# interaction_agronautes.net
KiCad netlist of a schematic drawn in EAGLE
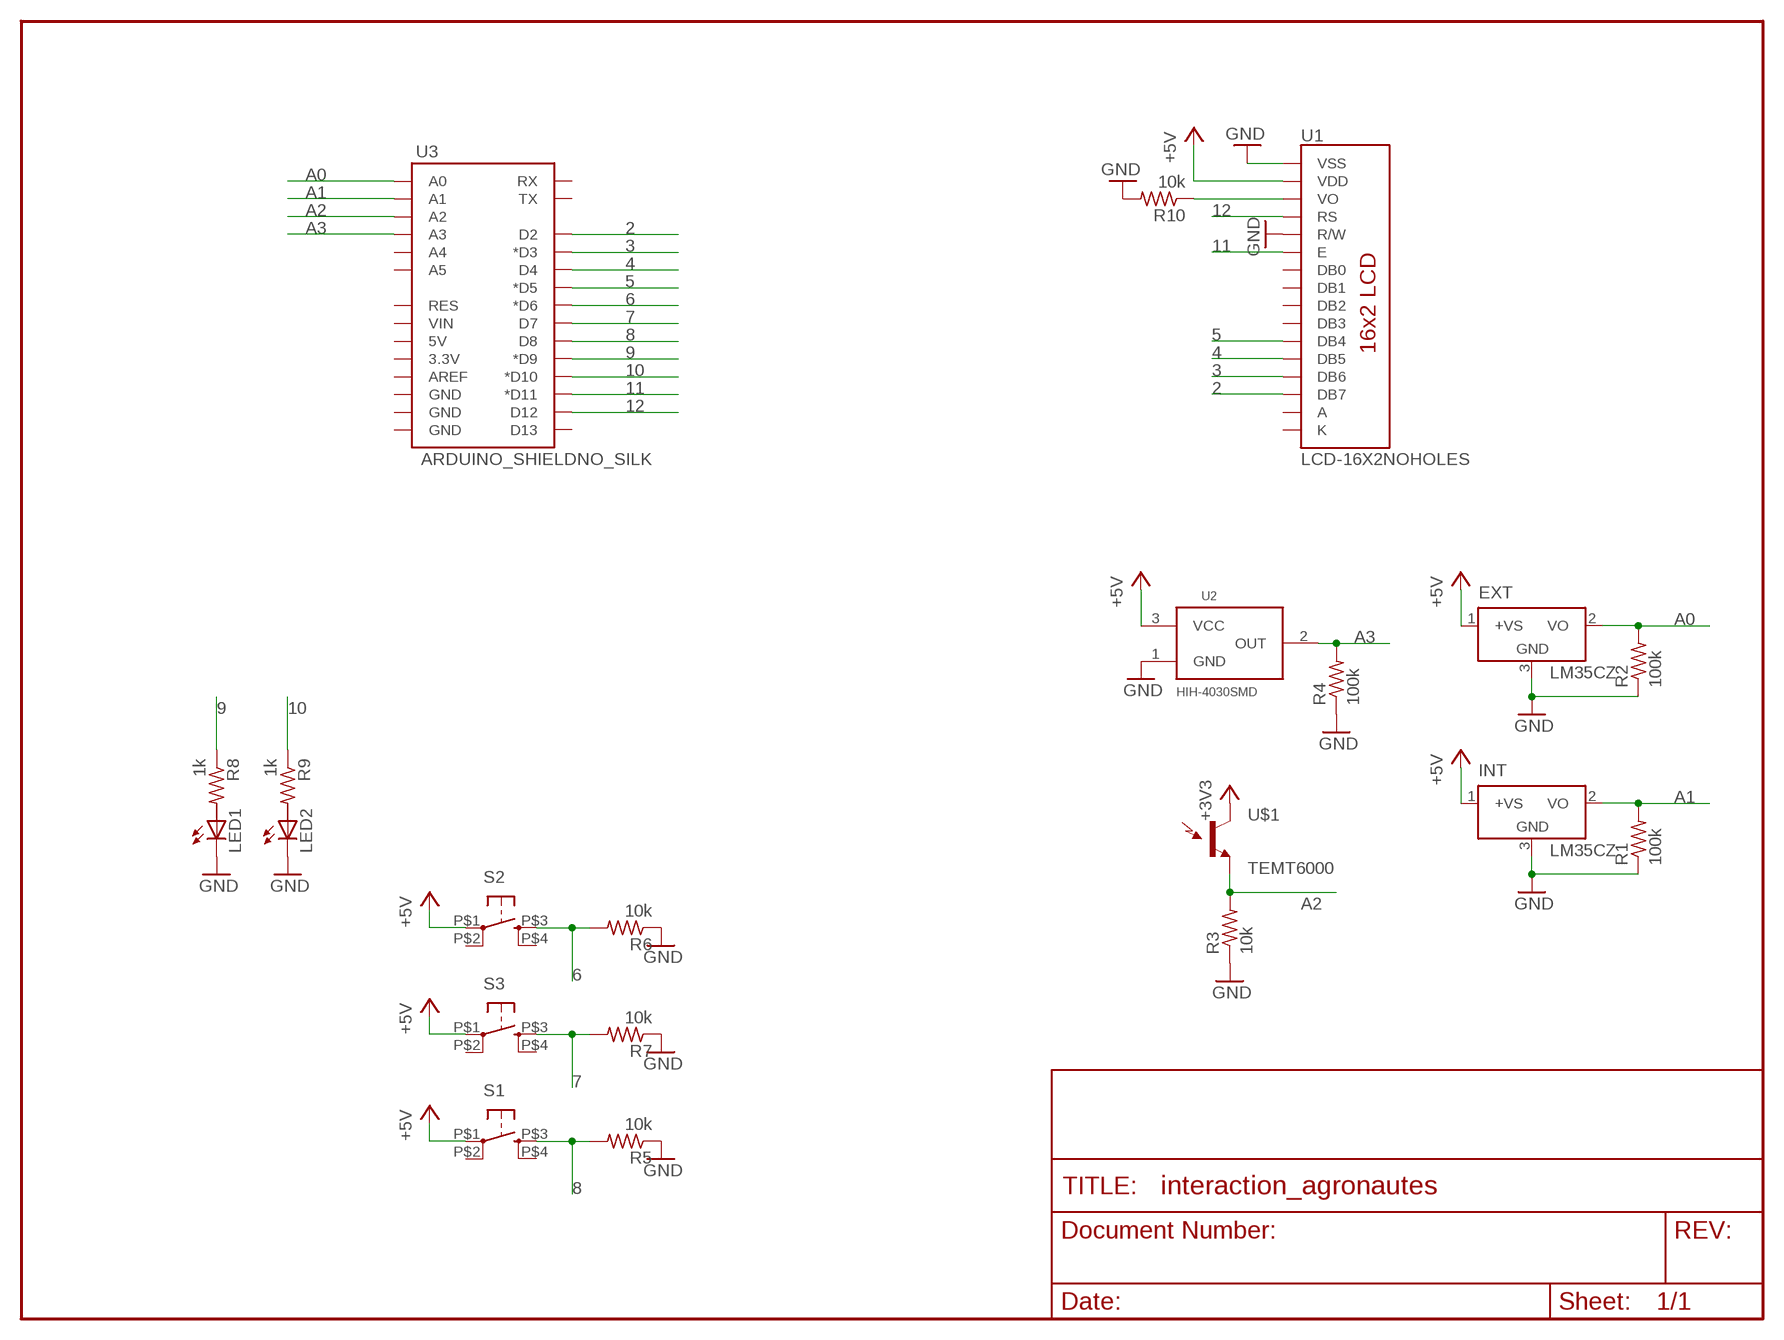
[diagram p0: schematic, sheet 1]

(export (version "E")
  (design (tool "Eeschema 10.0.6"))
  (components
    (comp (ref "EXT")
      (value "LM35CZ")
      (footprint "eagle-import:TO92")
      (libsource (lib "eagle-import") (part "LM35CZ"))
    )
    (comp (ref "INT")
      (value "LM35CZ")
      (footprint "eagle-import:TO92")
      (libsource (lib "eagle-import") (part "LM35CZ"))
    )
    (comp (ref "LED1")
      (value "LED5MM")
      (footprint "eagle-import:LED5MM")
      (libsource (lib "eagle-import") (part "LED5MM"))
    )
    (comp (ref "LED2")
      (value "LED5MM")
      (footprint "eagle-import:LED5MM")
      (libsource (lib "eagle-import") (part "LED5MM"))
    )
    (comp (ref "R1")
      (value "100k")
      (footprint "eagle-import:0204_7")
      (libsource (lib "eagle-import") (part "R-US_0204/7"))
    )
    (comp (ref "R2")
      (value "100k")
      (footprint "eagle-import:0204_7")
      (libsource (lib "eagle-import") (part "R-US_0204/7"))
    )
    (comp (ref "R3")
      (value "10k")
      (footprint "eagle-import:0204_7")
      (libsource (lib "eagle-import") (part "R-US_0204/7"))
    )
    (comp (ref "R4")
      (value "100k")
      (footprint "eagle-import:0204_7")
      (libsource (lib "eagle-import") (part "R-US_0204/7"))
    )
    (comp (ref "R5")
      (value "10k")
      (footprint "eagle-import:0204_7")
      (libsource (lib "eagle-import") (part "R-US_0204/7"))
    )
    (comp (ref "R6")
      (value "10k")
      (footprint "eagle-import:0204_7")
      (libsource (lib "eagle-import") (part "R-US_0204/7"))
    )
    (comp (ref "R7")
      (value "10k")
      (footprint "eagle-import:0204_7")
      (libsource (lib "eagle-import") (part "R-US_0204/7"))
    )
    (comp (ref "R8")
      (value "1k")
      (footprint "eagle-import:0204_7")
      (libsource (lib "eagle-import") (part "R-US_0204/7"))
    )
    (comp (ref "R9")
      (value "1k")
      (footprint "eagle-import:0204_7")
      (libsource (lib "eagle-import") (part "R-US_0204/7"))
    )
    (comp (ref "R10")
      (value "10k")
      (footprint "eagle-import:0204_7")
      (libsource (lib "eagle-import") (part "R-US_0204/7"))
    )
    (comp (ref "S1")
      (value "TAC_SWITCHKSA_SEALED")
      (footprint "eagle-import:KSA_SEALED_TAC_SWITCH")
      (libsource (lib "eagle-import") (part "TAC_SWITCHKSA_SEALED"))
    )
    (comp (ref "S2")
      (value "TAC_SWITCHKSA_SEALED")
      (footprint "eagle-import:KSA_SEALED_TAC_SWITCH")
      (libsource (lib "eagle-import") (part "TAC_SWITCHKSA_SEALED"))
    )
    (comp (ref "S3")
      (value "TAC_SWITCHKSA_SEALED")
      (footprint "eagle-import:KSA_SEALED_TAC_SWITCH")
      (libsource (lib "eagle-import") (part "TAC_SWITCHKSA_SEALED"))
    )
    (comp (ref "U$1")
      (value "TEMT6000")
      (footprint "eagle-import:TEMT6000-SEN")
      (libsource (lib "eagle-import") (part "TEMT6000"))
    )
    (comp (ref "U1")
      (value "LCD-16X2NOHOLES")
      (footprint "eagle-import:LCD-16X2_NOHOLES")
      (libsource (lib "eagle-import") (part "LCD-16X2NOHOLES"))
    )
    (comp (ref "U2")
      (value "HIH-4030SMD")
      (footprint "eagle-import:HIH-4030")
      (libsource (lib "eagle-import") (part "HIH-4030SMD"))
    )
    (comp (ref "U3")
      (value "ARDUINO_SHIELDNO_SILK")
      (footprint "eagle-import:DUEMILANOVE_VIAS")
      (libsource (lib "eagle-import") (part "ARDUINO_SHIELDNO_SILK"))
    )
  )
  (nets
    (net (code "1") (name "+3V3") (class "Default")
      (node (ref "U$1") (pin "COLLECTOR") (pinfunction "C1_COLLECTOR") (pintype "passive"))
    )
    (net (code "2") (name "+5V") (class "Default")
      (node (ref "EXT") (pin "1") (pinfunction "+VS_1") (pintype "input"))
      (node (ref "INT") (pin "1") (pinfunction "+VS_1") (pintype "input"))
      (node (ref "S1") (pin "P$1") (pinfunction "1_P$1") (pintype "passive"))
      (node (ref "S2") (pin "P$1") (pinfunction "1_P$1") (pintype "passive"))
      (node (ref "S3") (pin "P$1") (pinfunction "1_P$1") (pintype "passive"))
      (node (ref "U1") (pin "2") (pinfunction "VDD_2") (pintype "power_in"))
      (node (ref "U2") (pin "3") (pinfunction "VCC_3") (pintype "bidirectional"))
    )
    (net (code "3") (name "/2") (class "Default")
      (node (ref "U1") (pin "14") (pinfunction "DB7_14") (pintype "bidirectional"))
      (node (ref "U3") (pin "D2") (pinfunction "D2_D2") (pintype "bidirectional"))
    )
    (net (code "4") (name "/3") (class "Default")
      (node (ref "U1") (pin "13") (pinfunction "DB6_13") (pintype "bidirectional"))
      (node (ref "U3") (pin "D3") (pinfunction "*D3_D3") (pintype "bidirectional"))
    )
    (net (code "5") (name "/4") (class "Default")
      (node (ref "U1") (pin "12") (pinfunction "DB5_12") (pintype "bidirectional"))
      (node (ref "U3") (pin "D4") (pinfunction "D4_D4") (pintype "bidirectional"))
    )
    (net (code "6") (name "/5") (class "Default")
      (node (ref "U1") (pin "11") (pinfunction "DB4_11") (pintype "bidirectional"))
      (node (ref "U3") (pin "D5") (pinfunction "*D5_D5") (pintype "bidirectional"))
    )
    (net (code "7") (name "/6") (class "Default")
      (node (ref "R6") (pin "2") (pinfunction "2_2") (pintype "passive"))
      (node (ref "S2") (pin "P$3") (pinfunction "3_P$3") (pintype "passive"))
      (node (ref "U3") (pin "D6") (pinfunction "*D6_D6") (pintype "bidirectional"))
    )
    (net (code "8") (name "/7") (class "Default")
      (node (ref "R7") (pin "2") (pinfunction "2_2") (pintype "passive"))
      (node (ref "S3") (pin "P$3") (pinfunction "3_P$3") (pintype "passive"))
      (node (ref "U3") (pin "D7") (pinfunction "D7_D7") (pintype "bidirectional"))
    )
    (net (code "9") (name "/8") (class "Default")
      (node (ref "R5") (pin "2") (pinfunction "2_2") (pintype "passive"))
      (node (ref "S1") (pin "P$3") (pinfunction "3_P$3") (pintype "passive"))
      (node (ref "U3") (pin "D8") (pinfunction "D8_D8") (pintype "bidirectional"))
    )
    (net (code "10") (name "/9") (class "Default")
      (node (ref "R8") (pin "1") (pinfunction "1_1") (pintype "passive"))
      (node (ref "U3") (pin "D9") (pinfunction "*D9_D9") (pintype "bidirectional"))
    )
    (net (code "11") (name "/10") (class "Default")
      (node (ref "R9") (pin "1") (pinfunction "1_1") (pintype "passive"))
      (node (ref "U3") (pin "D10") (pinfunction "*D10_D10") (pintype "bidirectional"))
    )
    (net (code "12") (name "/11") (class "Default")
      (node (ref "U1") (pin "6") (pinfunction "E_6") (pintype "input"))
      (node (ref "U3") (pin "D11") (pinfunction "*D11_D11") (pintype "bidirectional"))
    )
    (net (code "13") (name "/12") (class "Default")
      (node (ref "U1") (pin "4") (pinfunction "RS_4") (pintype "input"))
      (node (ref "U3") (pin "D12") (pinfunction "D12_D12") (pintype "bidirectional"))
    )
    (net (code "14") (name "/A") (class "Default")
      (node (ref "U1") (pin "15") (pinfunction "A_15") (pintype "power_in"))
    )
    (net (code "15") (name "/A0") (class "Default")
      (node (ref "EXT") (pin "2") (pinfunction "VO_2") (pintype "input"))
      (node (ref "R2") (pin "2") (pinfunction "2_2") (pintype "passive"))
      (node (ref "U3") (pin "A0") (pinfunction "A0_A0") (pintype "bidirectional"))
    )
    (net (code "16") (name "/A1") (class "Default")
      (node (ref "INT") (pin "2") (pinfunction "VO_2") (pintype "input"))
      (node (ref "R1") (pin "2") (pinfunction "2_2") (pintype "passive"))
      (node (ref "U3") (pin "A1") (pinfunction "A1_A1") (pintype "bidirectional"))
    )
    (net (code "17") (name "/A2") (class "Default")
      (node (ref "R3") (pin "2") (pinfunction "2_2") (pintype "passive"))
      (node (ref "U$1") (pin "EMITTER") (pinfunction "E1_EMITTER") (pintype "passive"))
      (node (ref "U3") (pin "A2") (pinfunction "A2_A2") (pintype "bidirectional"))
    )
    (net (code "18") (name "/A3") (class "Default")
      (node (ref "R4") (pin "2") (pinfunction "2_2") (pintype "passive"))
      (node (ref "U2") (pin "2") (pinfunction "OUT_2") (pintype "bidirectional"))
      (node (ref "U3") (pin "A3") (pinfunction "A3_A3") (pintype "bidirectional"))
    )
    (net (code "19") (name "/K") (class "Default")
      (node (ref "U1") (pin "16") (pinfunction "K_16") (pintype "power_in"))
    )
    (net (code "20") (name "GND") (class "Default")
      (node (ref "EXT") (pin "3") (pinfunction "GND_3") (pintype "power_in"))
      (node (ref "INT") (pin "3") (pinfunction "GND_3") (pintype "power_in"))
      (node (ref "LED1") (pin "K") (pinfunction "C_K") (pintype "passive"))
      (node (ref "LED2") (pin "K") (pinfunction "C_K") (pintype "passive"))
      (node (ref "R1") (pin "1") (pinfunction "1_1") (pintype "passive"))
      (node (ref "R10") (pin "2") (pinfunction "2_2") (pintype "passive"))
      (node (ref "R2") (pin "1") (pinfunction "1_1") (pintype "passive"))
      (node (ref "R3") (pin "1") (pinfunction "1_1") (pintype "passive"))
      (node (ref "R4") (pin "1") (pinfunction "1_1") (pintype "passive"))
      (node (ref "R5") (pin "1") (pinfunction "1_1") (pintype "passive"))
      (node (ref "R6") (pin "1") (pinfunction "1_1") (pintype "passive"))
      (node (ref "R7") (pin "1") (pinfunction "1_1") (pintype "passive"))
      (node (ref "U1") (pin "1") (pinfunction "VSS_1") (pintype "power_in"))
      (node (ref "U1") (pin "5") (pinfunction "R/W_5") (pintype "input"))
      (node (ref "U2") (pin "1") (pinfunction "GND_1") (pintype "bidirectional"))
    )
    (net (code "21") (name "Net-(U1-VO)") (class "Default")
      (node (ref "R10") (pin "1") (pinfunction "1_1") (pintype "passive"))
      (node (ref "U1") (pin "3") (pinfunction "VO_3") (pintype "bidirectional"))
    )
    (net (code "22") (name "unconnected-(LED1-PadA)") (class "Default")
      (node (ref "LED1") (pin "A") (pinfunction "A_A") (pintype "passive"))
    )
    (net (code "23") (name "unconnected-(LED2-PadA)") (class "Default")
      (node (ref "LED2") (pin "A") (pinfunction "A_A") (pintype "passive"))
    )
    (net (code "24") (name "unconnected-(R8-Pad2)") (class "Default")
      (node (ref "R8") (pin "2") (pinfunction "2_2") (pintype "passive"))
    )
    (net (code "25") (name "unconnected-(R9-Pad2)") (class "Default")
      (node (ref "R9") (pin "2") (pinfunction "2_2") (pintype "passive"))
    )
    (net (code "26") (name "unconnected-(S1-2-PadP$2)") (class "Default")
      (node (ref "S1") (pin "P$2") (pinfunction "2_P$2") (pintype "passive"))
    )
    (net (code "27") (name "unconnected-(S1-4-PadP$4)") (class "Default")
      (node (ref "S1") (pin "P$4") (pinfunction "4_P$4") (pintype "passive"))
    )
    (net (code "28") (name "unconnected-(S2-2-PadP$2)") (class "Default")
      (node (ref "S2") (pin "P$2") (pinfunction "2_P$2") (pintype "passive"))
    )
    (net (code "29") (name "unconnected-(S2-4-PadP$4)") (class "Default")
      (node (ref "S2") (pin "P$4") (pinfunction "4_P$4") (pintype "passive"))
    )
    (net (code "30") (name "unconnected-(S3-2-PadP$2)") (class "Default")
      (node (ref "S3") (pin "P$2") (pinfunction "2_P$2") (pintype "passive"))
    )
    (net (code "31") (name "unconnected-(S3-4-PadP$4)") (class "Default")
      (node (ref "S3") (pin "P$4") (pinfunction "4_P$4") (pintype "passive"))
    )
    (net (code "32") (name "unconnected-(U1-DB0-Pad7)") (class "Default")
      (node (ref "U1") (pin "7") (pinfunction "DB0_7") (pintype "bidirectional"))
    )
    (net (code "33") (name "unconnected-(U1-DB1-Pad8)") (class "Default")
      (node (ref "U1") (pin "8") (pinfunction "DB1_8") (pintype "bidirectional"))
    )
    (net (code "34") (name "unconnected-(U1-DB2-Pad9)") (class "Default")
      (node (ref "U1") (pin "9") (pinfunction "DB2_9") (pintype "bidirectional"))
    )
    (net (code "35") (name "unconnected-(U1-DB3-Pad10)") (class "Default")
      (node (ref "U1") (pin "10") (pinfunction "DB3_10") (pintype "bidirectional"))
    )
    (net (code "36") (name "unconnected-(U3-GND-PadGND@0)") (class "Default")
      (node (ref "U3") (pin "GND@0") (pinfunction "GND_GND@0") (pintype "bidirectional"))
    )
    (net (code "37") (name "unconnected-(U3-GND-PadGND@1)") (class "Default")
      (node (ref "U3") (pin "GND@1") (pinfunction "GND_GND@1") (pintype "bidirectional"))
    )
    (net (code "38") (name "unconnected-(U3-GND-PadGND@2)") (class "Default")
      (node (ref "U3") (pin "GND@2") (pinfunction "GND_GND@2") (pintype "bidirectional"))
    )
    (net (code "39") (name "unconnected-(U3-Pad3.3V)") (class "Default")
      (node (ref "U3") (pin "3.3V") (pinfunction "3.3V_3.3V") (pintype "bidirectional"))
    )
    (net (code "40") (name "unconnected-(U3-Pad5V)") (class "Default")
      (node (ref "U3") (pin "5V") (pinfunction "5V_5V") (pintype "bidirectional"))
    )
    (net (code "41") (name "unconnected-(U3-PadA4)") (class "Default")
      (node (ref "U3") (pin "A4") (pinfunction "A4_A4") (pintype "bidirectional"))
    )
    (net (code "42") (name "unconnected-(U3-PadA5)") (class "Default")
      (node (ref "U3") (pin "A5") (pinfunction "A5_A5") (pintype "bidirectional"))
    )
    (net (code "43") (name "unconnected-(U3-PadAREF)") (class "Default")
      (node (ref "U3") (pin "AREF") (pinfunction "AREF_AREF") (pintype "bidirectional"))
    )
    (net (code "44") (name "unconnected-(U3-PadD13)") (class "Default")
      (node (ref "U3") (pin "D13") (pinfunction "D13_D13") (pintype "bidirectional"))
    )
    (net (code "45") (name "unconnected-(U3-PadRES)") (class "Default")
      (node (ref "U3") (pin "RES") (pinfunction "RES_RES") (pintype "bidirectional"))
    )
    (net (code "46") (name "unconnected-(U3-PadRX)") (class "Default")
      (node (ref "U3") (pin "RX") (pinfunction "RX_RX") (pintype "bidirectional"))
    )
    (net (code "47") (name "unconnected-(U3-PadTX)") (class "Default")
      (node (ref "U3") (pin "TX") (pinfunction "TX_TX") (pintype "bidirectional"))
    )
    (net (code "48") (name "unconnected-(U3-PadVIN)") (class "Default")
      (node (ref "U3") (pin "VIN") (pinfunction "VIN_VIN") (pintype "bidirectional"))
    )
  )
)
